# DoorSensor.net
KiCad netlist of a schematic drawn in Altium Designer
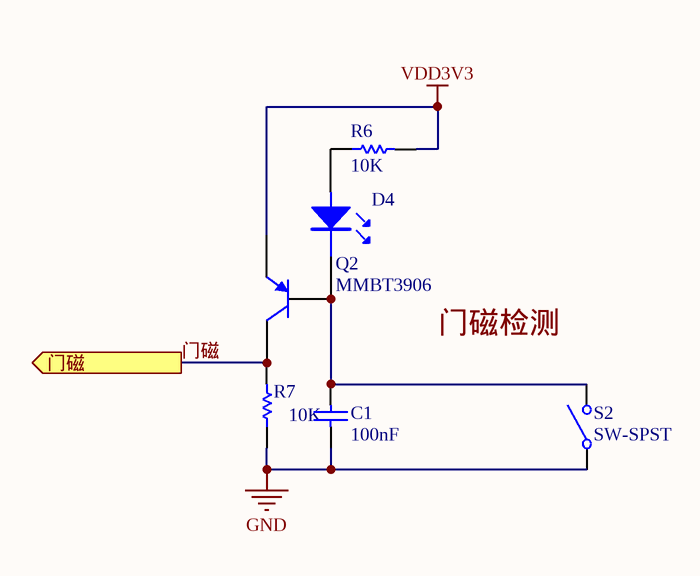
[diagram p0: DoorSensor.SchDoc]

(export (version "E")
  (design (tool "Eeschema 10.0.6"))
  (components
    (comp (ref "C1")
      (value "100nF")
      (footprint "CAPC0805(2012)100_L")
      (description "CAP 100nF 50V ±5% 0805 (2012 Metric) Thickness 1mm SMD")
      (fields (field (name "TOLERANCE") "±5%") (field (name "Comment") "CAP 100nF 50V 0805(2012)"))
      (libsource (lib "Altium Content Vault") (part "CMP-1036-04418-1"))
    )
    (comp (ref "D4") (value "~") (footprint "0805-L") (libsource (lib "*") (part "LED")))
    (comp (ref "Q2")
      (value "MMBT3906")
      (footprint "SOT23_N")
      (description "PNP Switching Transistor")
      (fields (field (name "PUBLISHER") "Altium Limited"))
      (libsource (lib "Philips Discrete BJT - Low Power") (part "MMBT3906"))
    )
    (comp (ref "R6")
      (value "10K")
      (footprint "RESC0805(2012)_M")
      (description "10K 0.125W 1% 0805 (2012 Metric)  SMD")
      (fields (field (name "TOLERANCE") "1 %") (field (name "POWER") "0.125 W"))
      (libsource (lib "Altium Content Vault") (part "CMP-1013-00623-1"))
    )
    (comp (ref "R7")
      (value "10K")
      (footprint "RESC0805(2012)_M")
      (description "10K 0.125W 1% 0805 (2012 Metric)  SMD")
      (fields (field (name "TOLERANCE") "1 %") (field (name "POWER") "0.125 W"))
      (libsource (lib "Altium Content Vault") (part "CMP-1013-00623-1"))
    )
    (comp (ref "S2")
      (value "SW-SPST")
      (footprint "SPST-2")
      (description "Single-Pole, Single-Throw Switch")
      (fields (field (name "PUBLISHER") "Altium Limited"))
      (libsource (lib "Miscellaneous Devices") (part "SW-SPST"))
    )
  )
  (nets
    (net (code "1") (name "/门磁") (class "Default")
      (node (ref "Q2") (pin "3") (pinfunction "C_3") (pintype "passive"))
      (node (ref "R7") (pin "2") (pinfunction "2_2") (pintype "passive"))
    )
    (net (code "2") (name "GND") (class "Default")
      (node (ref "C1") (pin "1") (pinfunction "1_1") (pintype "passive"))
      (node (ref "R7") (pin "1") (pinfunction "1_1") (pintype "passive"))
      (node (ref "S2") (pin "1") (pinfunction "COMMON_1") (pintype "passive"))
    )
    (net (code "3") (name "Net-(D4-Pad1)") (class "Default")
      (node (ref "D4") (pin "1") (pinfunction "1_1") (pintype "passive"))
      (node (ref "R6") (pin "1") (pinfunction "1_1") (pintype "passive"))
    )
    (net (code "4") (name "Net-(Q2-B)") (class "Default")
      (node (ref "C1") (pin "2") (pinfunction "2_2") (pintype "passive"))
      (node (ref "D4") (pin "2") (pinfunction "2_2") (pintype "passive"))
      (node (ref "Q2") (pin "1") (pinfunction "B_1") (pintype "passive"))
      (node (ref "S2") (pin "2") (pinfunction "NO_2") (pintype "passive"))
    )
    (net (code "5") (name "VDD3V3") (class "Default")
      (node (ref "Q2") (pin "2") (pinfunction "E_2") (pintype "passive"))
      (node (ref "R6") (pin "2") (pinfunction "2_2") (pintype "passive"))
    )
  )
)
